# fm_radio.net
KiCad netlist of a schematic drawn in EAGLE
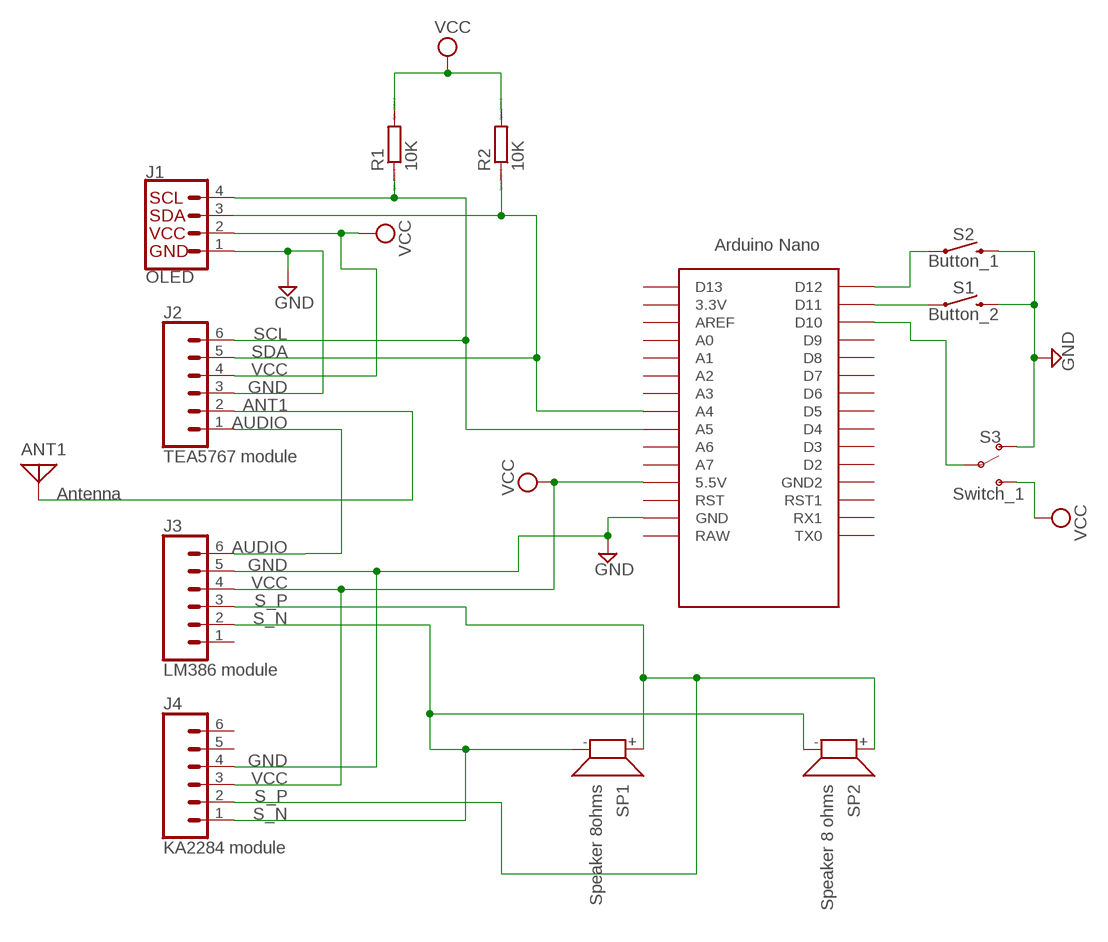
[diagram p0: schematic, sheet 1]

(export (version "E")
  (design (tool "Eeschema 10.0.6"))
  (components
    (comp (ref "ANT1")
      (value "Antenna")
      (footprint "eagle-import:PAD-01")
      (libsource (lib "eagle-import") (part "ANTENNA"))
    )
    (comp (ref "J1")
      (value "OLED")
      (footprint "eagle-import:1X04_NO_SILK")
      (libsource (lib "eagle-import") (part "I2C_STANDARD_NO_SILK"))
    )
    (comp (ref "J2")
      (value "TEA5767 module")
      (footprint "eagle-import:1X06_1.27MM")
      (libsource (lib "eagle-import") (part "CONN_061.27MM"))
    )
    (comp (ref "J3")
      (value "LM386 module")
      (footprint "eagle-import:1X06_1.27MM")
      (libsource (lib "eagle-import") (part "CONN_061.27MM"))
    )
    (comp (ref "J4")
      (value "KA2284 module")
      (footprint "eagle-import:1X06_1.27MM")
      (libsource (lib "eagle-import") (part "CONN_061.27MM"))
    )
    (comp (ref "R1")
      (value "10K")
      (footprint "eagle-import:R0603")
      (libsource (lib "eagle-import") (part "RR0603"))
    )
    (comp (ref "R2")
      (value "10K")
      (footprint "eagle-import:R0603")
      (libsource (lib "eagle-import") (part "RR0603"))
    )
    (comp (ref "S1")
      (value "Button_2")
      (footprint "eagle-import:TACTILE_SWITCH_PTH_6.0MM")
      (libsource (lib "eagle-import") (part "MOMENTARY-SWITCH-SPST-PTH-6.0MM"))
    )
    (comp (ref "S2")
      (value "Button_1")
      (footprint "eagle-import:TACTILE_SWITCH_PTH_6.0MM")
      (libsource (lib "eagle-import") (part "MOMENTARY-SWITCH-SPST-PTH-6.0MM"))
    )
    (comp (ref "S3")
      (value "Switch_1")
      (footprint "eagle-import:SWITCH_DPDT_SMD_AYZ0202")
      (libsource (lib "eagle-import") (part "SWITCH-SPDT-SMD-AYZ0202"))
    )
    (comp (ref "SP1")
      (value "Speaker 8ohms")
      (footprint "eagle-import:SMS-1308MS-2-R")
      (libsource (lib "eagle-import") (part "SMS-1308MS-2-R"))
    )
    (comp (ref "SP2")
      (value "Speaker 8 ohms")
      (footprint "eagle-import:SMS-1308MS-2-R")
      (libsource (lib "eagle-import") (part "SMS-1308MS-2-R"))
    )
    (comp (ref "U$1")
      (value "NANO")
      (footprint "eagle-import:NANO")
      (libsource (lib "eagle-import") (part "NANO"))
    )
  )
  (nets
    (net (code "1") (name "/ANT1") (class "Default")
      (node (ref "ANT1") (pin "1") (pinfunction "1_1") (pintype "output"))
      (node (ref "J2") (pin "2") (pinfunction "2_2") (pintype "passive"))
    )
    (net (code "2") (name "/AUDIO") (class "Default")
      (node (ref "J2") (pin "1") (pinfunction "1_1") (pintype "passive"))
      (node (ref "J3") (pin "6") (pinfunction "6_6") (pintype "passive"))
    )
    (net (code "3") (name "/SCL") (class "Default")
      (node (ref "J1") (pin "4") (pinfunction "4_4") (pintype "passive"))
      (node (ref "J2") (pin "6") (pinfunction "6_6") (pintype "passive"))
      (node (ref "R1") (pin "1") (pinfunction "1_1") (pintype "passive"))
      (node (ref "U$1") (pin "A5") (pinfunction "A5_A5") (pintype "bidirectional"))
    )
    (net (code "4") (name "/SDA") (class "Default")
      (node (ref "J1") (pin "3") (pinfunction "3_3") (pintype "passive"))
      (node (ref "J2") (pin "5") (pinfunction "5_5") (pintype "passive"))
      (node (ref "R2") (pin "1") (pinfunction "1_1") (pintype "passive"))
      (node (ref "U$1") (pin "A4") (pinfunction "A4_A4") (pintype "bidirectional"))
    )
    (net (code "5") (name "/S_N") (class "Default")
      (node (ref "J3") (pin "2") (pinfunction "2_2") (pintype "passive"))
      (node (ref "J4") (pin "1") (pinfunction "1_1") (pintype "passive"))
      (node (ref "SP1") (pin "-") (pinfunction "2_-") (pintype "passive"))
      (node (ref "SP2") (pin "-") (pinfunction "2_-") (pintype "passive"))
    )
    (net (code "6") (name "/S_P") (class "Default")
      (node (ref "J3") (pin "3") (pinfunction "3_3") (pintype "passive"))
      (node (ref "J4") (pin "2") (pinfunction "2_2") (pintype "passive"))
      (node (ref "SP1") (pin "+") (pinfunction "1_+") (pintype "passive"))
      (node (ref "SP2") (pin "+") (pinfunction "1_+") (pintype "passive"))
    )
    (net (code "7") (name "GND") (class "Default")
      (node (ref "J1") (pin "1") (pinfunction "1_1") (pintype "power_in"))
      (node (ref "J2") (pin "3") (pinfunction "3_3") (pintype "passive"))
      (node (ref "J3") (pin "5") (pinfunction "5_5") (pintype "passive"))
      (node (ref "J4") (pin "4") (pinfunction "4_4") (pintype "passive"))
      (node (ref "S1") (pin "3") (pinfunction "2_3") (pintype "passive"))
      (node (ref "S2") (pin "3") (pinfunction "2_3") (pintype "passive"))
      (node (ref "S3") (pin "1") (pinfunction "O_1") (pintype "passive"))
      (node (ref "U$1") (pin "GND") (pinfunction "GND_GND") (pintype "bidirectional"))
    )
    (net (code "8") (name "Net-(S1-Pad1)") (class "Default")
      (node (ref "S1") (pin "1") (pinfunction "1_1") (pintype "passive"))
      (node (ref "U$1") (pin "D11") (pinfunction "D11_D11") (pintype "bidirectional"))
    )
    (net (code "9") (name "Net-(S2-Pad1)") (class "Default")
      (node (ref "S2") (pin "1") (pinfunction "1_1") (pintype "passive"))
      (node (ref "U$1") (pin "D12") (pinfunction "D12_D12") (pintype "bidirectional"))
    )
    (net (code "10") (name "Net-(S3-P)") (class "Default")
      (node (ref "S3") (pin "2") (pinfunction "P_2") (pintype "passive"))
      (node (ref "U$1") (pin "D10") (pinfunction "D10_D10") (pintype "bidirectional"))
    )
    (net (code "11") (name "VCC") (class "Default")
      (node (ref "J1") (pin "2") (pinfunction "2_2") (pintype "power_in"))
      (node (ref "J2") (pin "4") (pinfunction "4_4") (pintype "passive"))
      (node (ref "J3") (pin "4") (pinfunction "4_4") (pintype "passive"))
      (node (ref "J4") (pin "3") (pinfunction "3_3") (pintype "passive"))
      (node (ref "R1") (pin "2") (pinfunction "2_2") (pintype "passive"))
      (node (ref "R2") (pin "2") (pinfunction "2_2") (pintype "passive"))
      (node (ref "S3") (pin "3") (pinfunction "S_3") (pintype "passive"))
      (node (ref "U$1") (pin "5V") (pinfunction "5.5V_5V") (pintype "bidirectional"))
    )
    (net (code "12") (name "unconnected-(J3-Pad1)") (class "Default")
      (node (ref "J3") (pin "1") (pinfunction "1_1") (pintype "passive"))
    )
    (net (code "13") (name "unconnected-(J4-Pad5)") (class "Default")
      (node (ref "J4") (pin "5") (pinfunction "5_5") (pintype "passive"))
    )
    (net (code "14") (name "unconnected-(J4-Pad6)") (class "Default")
      (node (ref "J4") (pin "6") (pinfunction "6_6") (pintype "passive"))
    )
    (net (code "15") (name "unconnected-(U$1-GND2-PadGND1)") (class "Default")
      (node (ref "U$1") (pin "GND1") (pinfunction "GND2_GND1") (pintype "bidirectional"))
    )
    (net (code "16") (name "unconnected-(U$1-Pad3.3V)") (class "Default")
      (node (ref "U$1") (pin "3.3V") (pinfunction "3.3V_3.3V") (pintype "bidirectional"))
    )
    (net (code "17") (name "unconnected-(U$1-PadA0)") (class "Default")
      (node (ref "U$1") (pin "A0") (pinfunction "A0_A0") (pintype "bidirectional"))
    )
    (net (code "18") (name "unconnected-(U$1-PadA1)") (class "Default")
      (node (ref "U$1") (pin "A1") (pinfunction "A1_A1") (pintype "bidirectional"))
    )
    (net (code "19") (name "unconnected-(U$1-PadA2)") (class "Default")
      (node (ref "U$1") (pin "A2") (pinfunction "A2_A2") (pintype "bidirectional"))
    )
    (net (code "20") (name "unconnected-(U$1-PadA3)") (class "Default")
      (node (ref "U$1") (pin "A3") (pinfunction "A3_A3") (pintype "bidirectional"))
    )
    (net (code "21") (name "unconnected-(U$1-PadA6)") (class "Default")
      (node (ref "U$1") (pin "A6") (pinfunction "A6_A6") (pintype "bidirectional"))
    )
    (net (code "22") (name "unconnected-(U$1-PadA7)") (class "Default")
      (node (ref "U$1") (pin "A7") (pinfunction "A7_A7") (pintype "bidirectional"))
    )
    (net (code "23") (name "unconnected-(U$1-PadAREF)") (class "Default")
      (node (ref "U$1") (pin "AREF") (pinfunction "AREF_AREF") (pintype "bidirectional"))
    )
    (net (code "24") (name "unconnected-(U$1-PadD2)") (class "Default")
      (node (ref "U$1") (pin "D2") (pinfunction "D2_D2") (pintype "bidirectional"))
    )
    (net (code "25") (name "unconnected-(U$1-PadD3)") (class "Default")
      (node (ref "U$1") (pin "D3") (pinfunction "D3_D3") (pintype "bidirectional"))
    )
    (net (code "26") (name "unconnected-(U$1-PadD4)") (class "Default")
      (node (ref "U$1") (pin "D4") (pinfunction "D4_D4") (pintype "bidirectional"))
    )
    (net (code "27") (name "unconnected-(U$1-PadD5)") (class "Default")
      (node (ref "U$1") (pin "D5") (pinfunction "D5_D5") (pintype "bidirectional"))
    )
    (net (code "28") (name "unconnected-(U$1-PadD6)") (class "Default")
      (node (ref "U$1") (pin "D6") (pinfunction "D6_D6") (pintype "bidirectional"))
    )
    (net (code "29") (name "unconnected-(U$1-PadD7)") (class "Default")
      (node (ref "U$1") (pin "D7") (pinfunction "D7_D7") (pintype "bidirectional"))
    )
    (net (code "30") (name "unconnected-(U$1-PadD8)") (class "Default")
      (node (ref "U$1") (pin "D8") (pinfunction "D8_D8") (pintype "bidirectional"))
    )
    (net (code "31") (name "unconnected-(U$1-PadD9)") (class "Default")
      (node (ref "U$1") (pin "D9") (pinfunction "D9_D9") (pintype "bidirectional"))
    )
    (net (code "32") (name "unconnected-(U$1-PadD13)") (class "Default")
      (node (ref "U$1") (pin "D13") (pinfunction "D13_D13") (pintype "bidirectional"))
    )
    (net (code "33") (name "unconnected-(U$1-PadICSP1)") (class "Default")
      (node (ref "U$1") (pin "ICSP1") (pinfunction "ICSP1_ICSP1") (pintype "bidirectional"))
    )
    (net (code "34") (name "unconnected-(U$1-PadICSP2)") (class "Default")
      (node (ref "U$1") (pin "ICSP2") (pinfunction "ICSP2_ICSP2") (pintype "bidirectional"))
    )
    (net (code "35") (name "unconnected-(U$1-PadICSP3)") (class "Default")
      (node (ref "U$1") (pin "ICSP3") (pinfunction "ICSP3_ICSP3") (pintype "bidirectional"))
    )
    (net (code "36") (name "unconnected-(U$1-PadICSP4)") (class "Default")
      (node (ref "U$1") (pin "ICSP4") (pinfunction "ICSP4_ICSP4") (pintype "bidirectional"))
    )
    (net (code "37") (name "unconnected-(U$1-PadICSP5)") (class "Default")
      (node (ref "U$1") (pin "ICSP5") (pinfunction "ICSP5_ICSP5") (pintype "bidirectional"))
    )
    (net (code "38") (name "unconnected-(U$1-PadICSP6)") (class "Default")
      (node (ref "U$1") (pin "ICSP6") (pinfunction "ICSP6_ICSP6") (pintype "bidirectional"))
    )
    (net (code "39") (name "unconnected-(U$1-PadRAW)") (class "Default")
      (node (ref "U$1") (pin "RAW") (pinfunction "RAW_RAW") (pintype "bidirectional"))
    )
    (net (code "40") (name "unconnected-(U$1-PadRST)") (class "Default")
      (node (ref "U$1") (pin "RST") (pinfunction "RST_RST") (pintype "bidirectional"))
    )
    (net (code "41") (name "unconnected-(U$1-PadRST1)") (class "Default")
      (node (ref "U$1") (pin "RST1") (pinfunction "RST1_RST1") (pintype "bidirectional"))
    )
    (net (code "42") (name "unconnected-(U$1-PadRX1)") (class "Default")
      (node (ref "U$1") (pin "RX1") (pinfunction "RX1_RX1") (pintype "bidirectional"))
    )
    (net (code "43") (name "unconnected-(U$1-PadTX0)") (class "Default")
      (node (ref "U$1") (pin "TX0") (pinfunction "TX0_TX0") (pintype "bidirectional"))
    )
  )
)
